# 08_FPGA.net
KiCad netlist of a schematic drawn in Altium Designer
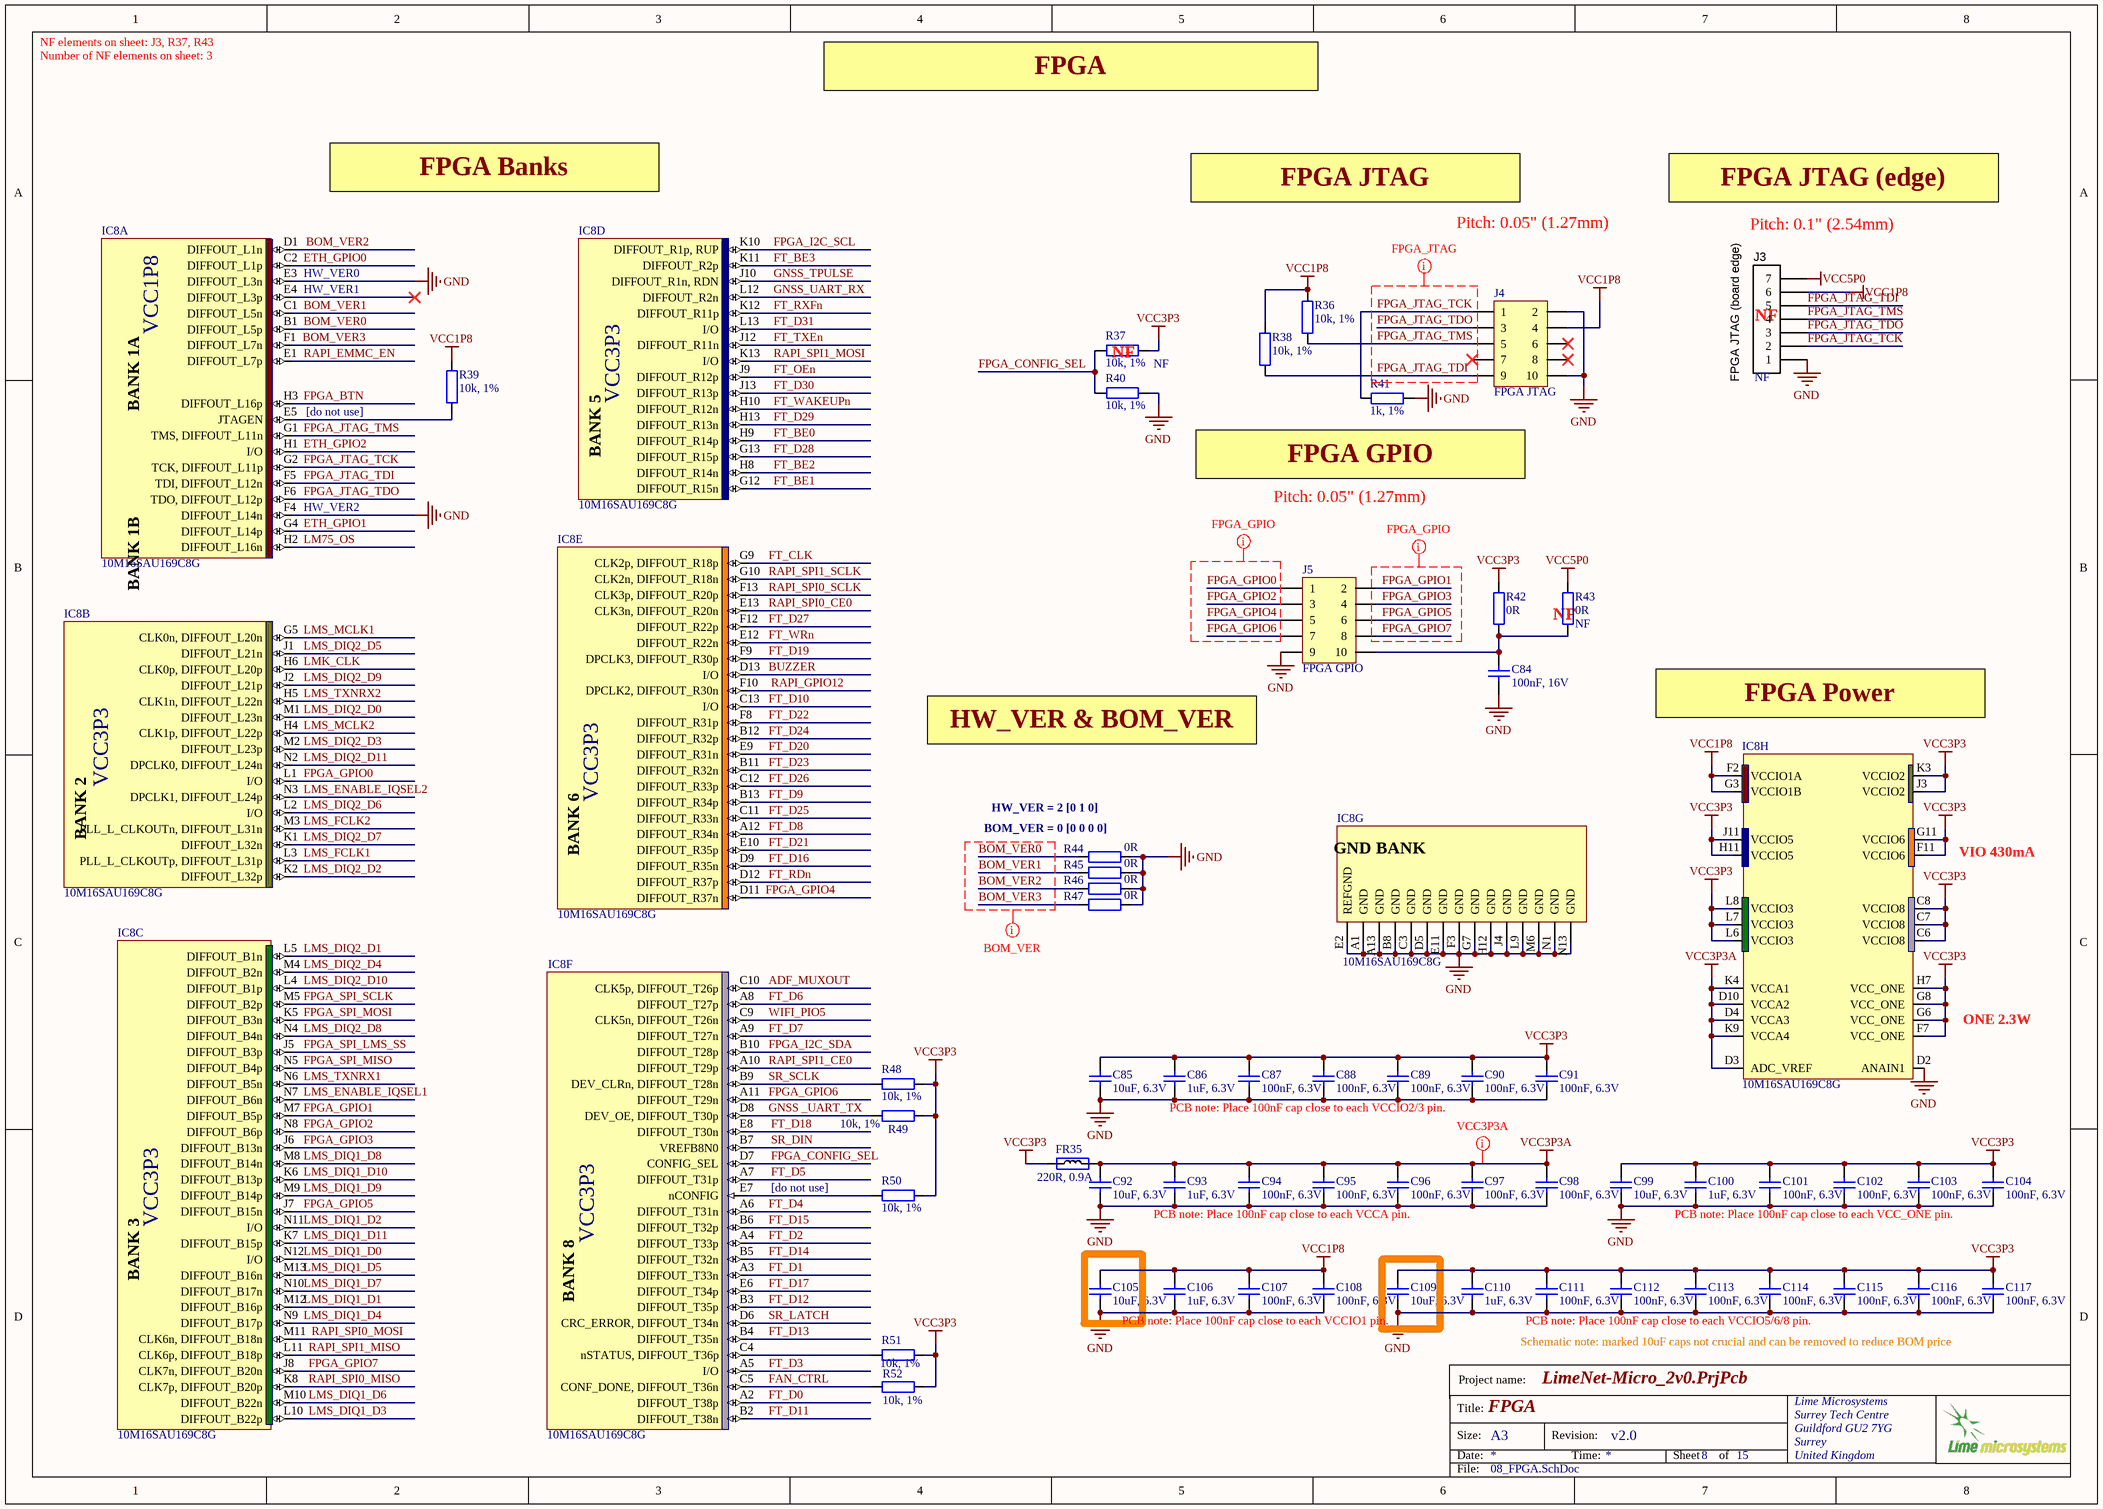
[diagram p0: 08_FPGA.SchDoc]

(export (version "E")
  (design (tool "Eeschema 10.0.6"))
  (components
    (comp (ref "C84")
      (value "100nF, 16V")
      (footprint "CAP0402")
      (fields
        (field (name "MANUFACTURER") "Murata Electronics")
        (field (name "TOLERANCE") "10 %")
        (field (name "MANUFACTURER PART NUMBER") "GRM155R71C104KA88D")
      )
      (libsource (lib "LimeMicroAltiumLib_schLib") (part "Cap_0402"))
    )
    (comp (ref "C85")
      (value "10uF, 6.3V")
      (footprint "CAP0603")
      (fields (field (name "TOLERANCE") "±20%") (field (name "MANUFACTURER") "Yageo"))
      (libsource (lib "LimeFPGAboard_schLib") (part "Cap_0603"))
    )
    (comp (ref "C86")
      (value "1uF, 6.3V")
      (footprint "CAP0201")
      (fields (field (name "TOLERANCE") "±20%") (field (name "MANUFACTURER") "TDK Corporation"))
      (libsource (lib "LimeMicroAltiumLib_schLib") (part "Cap_0402"))
    )
    (comp (ref "C87")
      (value "100nF, 6.3V")
      (footprint "CAP0201")
      (fields (field (name "MANUFACTURER") "Murata") (field (name "TOLERANCE") "10 %"))
      (libsource (lib "LimeMicroAltiumLib_schLib") (part "Cap_0402"))
    )
    (comp (ref "C88")
      (value "100nF, 6.3V")
      (footprint "CAP0201")
      (fields (field (name "MANUFACTURER") "Murata") (field (name "TOLERANCE") "10 %"))
      (libsource (lib "LimeMicroAltiumLib_schLib") (part "Cap_0402"))
    )
    (comp (ref "C89")
      (value "100nF, 6.3V")
      (footprint "CAP0201")
      (fields (field (name "MANUFACTURER") "Murata") (field (name "TOLERANCE") "10 %"))
      (libsource (lib "LimeMicroAltiumLib_schLib") (part "Cap_0402"))
    )
    (comp (ref "C90")
      (value "100nF, 6.3V")
      (footprint "CAP0201")
      (fields (field (name "MANUFACTURER") "Murata") (field (name "TOLERANCE") "10 %"))
      (libsource (lib "LimeMicroAltiumLib_schLib") (part "Cap_0402"))
    )
    (comp (ref "C91")
      (value "100nF, 6.3V")
      (footprint "CAP0201")
      (fields (field (name "MANUFACTURER") "Murata") (field (name "TOLERANCE") "10 %"))
      (libsource (lib "LimeMicroAltiumLib_schLib") (part "Cap_0402"))
    )
    (comp (ref "C92")
      (value "10uF, 6.3V")
      (footprint "CAP0603")
      (fields (field (name "TOLERANCE") "±20%") (field (name "MANUFACTURER") "Yageo"))
      (libsource (lib "LimeFPGAboard_schLib") (part "Cap_0603"))
    )
    (comp (ref "C93")
      (value "1uF, 6.3V")
      (footprint "CAP0201")
      (fields (field (name "TOLERANCE") "±20%") (field (name "MANUFACTURER") "TDK Corporation"))
      (libsource (lib "LimeMicroAltiumLib_schLib") (part "Cap_0402"))
    )
    (comp (ref "C94")
      (value "100nF, 6.3V")
      (footprint "CAP0201")
      (fields (field (name "MANUFACTURER") "Murata") (field (name "TOLERANCE") "10 %"))
      (libsource (lib "LimeMicroAltiumLib_schLib") (part "Cap_0402"))
    )
    (comp (ref "C95")
      (value "100nF, 6.3V")
      (footprint "CAP0201")
      (fields (field (name "MANUFACTURER") "Murata") (field (name "TOLERANCE") "10 %"))
      (libsource (lib "LimeMicroAltiumLib_schLib") (part "Cap_0402"))
    )
    (comp (ref "C96")
      (value "100nF, 6.3V")
      (footprint "CAP0201")
      (fields (field (name "MANUFACTURER") "Murata") (field (name "TOLERANCE") "10 %"))
      (libsource (lib "LimeMicroAltiumLib_schLib") (part "Cap_0402"))
    )
    (comp (ref "C97")
      (value "100nF, 6.3V")
      (footprint "CAP0201")
      (fields (field (name "MANUFACTURER") "Murata") (field (name "TOLERANCE") "10 %"))
      (libsource (lib "LimeMicroAltiumLib_schLib") (part "Cap_0402"))
    )
    (comp (ref "C98")
      (value "100nF, 6.3V")
      (footprint "CAP0201")
      (fields (field (name "MANUFACTURER") "Murata") (field (name "TOLERANCE") "10 %"))
      (libsource (lib "LimeMicroAltiumLib_schLib") (part "Cap_0402"))
    )
    (comp (ref "C99")
      (value "10uF, 6.3V")
      (footprint "CAP0603")
      (fields (field (name "TOLERANCE") "±20%") (field (name "MANUFACTURER") "Yageo"))
      (libsource (lib "LimeFPGAboard_schLib") (part "Cap_0603"))
    )
    (comp (ref "C100")
      (value "1uF, 6.3V")
      (footprint "CAP0201")
      (fields (field (name "TOLERANCE") "±20%") (field (name "MANUFACTURER") "TDK Corporation"))
      (libsource (lib "LimeMicroAltiumLib_schLib") (part "Cap_0402"))
    )
    (comp (ref "C101")
      (value "100nF, 6.3V")
      (footprint "CAP0201")
      (fields (field (name "MANUFACTURER") "Murata") (field (name "TOLERANCE") "10 %"))
      (libsource (lib "LimeMicroAltiumLib_schLib") (part "Cap_0402"))
    )
    (comp (ref "C102")
      (value "100nF, 6.3V")
      (footprint "CAP0201")
      (fields (field (name "MANUFACTURER") "Murata") (field (name "TOLERANCE") "10 %"))
      (libsource (lib "LimeMicroAltiumLib_schLib") (part "Cap_0402"))
    )
    (comp (ref "C103")
      (value "100nF, 6.3V")
      (footprint "CAP0201")
      (fields (field (name "MANUFACTURER") "Murata") (field (name "TOLERANCE") "10 %"))
      (libsource (lib "LimeMicroAltiumLib_schLib") (part "Cap_0402"))
    )
    (comp (ref "C104")
      (value "100nF, 6.3V")
      (footprint "CAP0201")
      (fields (field (name "MANUFACTURER") "Murata") (field (name "TOLERANCE") "10 %"))
      (libsource (lib "LimeMicroAltiumLib_schLib") (part "Cap_0402"))
    )
    (comp (ref "C105")
      (value "10uF, 6.3V")
      (footprint "CAP0603")
      (fields (field (name "TOLERANCE") "±20%") (field (name "MANUFACTURER") "Yageo"))
      (libsource (lib "LimeFPGAboard_schLib") (part "Cap_0603"))
    )
    (comp (ref "C106")
      (value "1uF, 6.3V")
      (footprint "CAP0201")
      (fields (field (name "TOLERANCE") "±20%") (field (name "MANUFACTURER") "TDK Corporation"))
      (libsource (lib "LimeMicroAltiumLib_schLib") (part "Cap_0402"))
    )
    (comp (ref "C107")
      (value "100nF, 6.3V")
      (footprint "CAP0201")
      (fields (field (name "MANUFACTURER") "Murata") (field (name "TOLERANCE") "10 %"))
      (libsource (lib "LimeMicroAltiumLib_schLib") (part "Cap_0402"))
    )
    (comp (ref "C108")
      (value "100nF, 6.3V")
      (footprint "CAP0201")
      (fields (field (name "MANUFACTURER") "Murata") (field (name "TOLERANCE") "10 %"))
      (libsource (lib "LimeMicroAltiumLib_schLib") (part "Cap_0402"))
    )
    (comp (ref "C109")
      (value "10uF, 6.3V")
      (footprint "CAP0603")
      (fields (field (name "TOLERANCE") "±20%") (field (name "MANUFACTURER") "Yageo"))
      (libsource (lib "LimeFPGAboard_schLib") (part "Cap_0603"))
    )
    (comp (ref "C110")
      (value "1uF, 6.3V")
      (footprint "CAP0201")
      (fields (field (name "TOLERANCE") "±20%") (field (name "MANUFACTURER") "TDK Corporation"))
      (libsource (lib "LimeMicroAltiumLib_schLib") (part "Cap_0402"))
    )
    (comp (ref "C111")
      (value "100nF, 6.3V")
      (footprint "CAP0201")
      (fields (field (name "MANUFACTURER") "Murata") (field (name "TOLERANCE") "10 %"))
      (libsource (lib "LimeMicroAltiumLib_schLib") (part "Cap_0402"))
    )
    (comp (ref "C112")
      (value "100nF, 6.3V")
      (footprint "CAP0201")
      (fields (field (name "MANUFACTURER") "Murata") (field (name "TOLERANCE") "10 %"))
      (libsource (lib "LimeMicroAltiumLib_schLib") (part "Cap_0402"))
    )
    (comp (ref "C113")
      (value "100nF, 6.3V")
      (footprint "CAP0201")
      (fields (field (name "MANUFACTURER") "Murata") (field (name "TOLERANCE") "10 %"))
      (libsource (lib "LimeMicroAltiumLib_schLib") (part "Cap_0402"))
    )
    (comp (ref "C114")
      (value "100nF, 6.3V")
      (footprint "CAP0201")
      (fields (field (name "MANUFACTURER") "Murata") (field (name "TOLERANCE") "10 %"))
      (libsource (lib "LimeMicroAltiumLib_schLib") (part "Cap_0402"))
    )
    (comp (ref "C115")
      (value "100nF, 6.3V")
      (footprint "CAP0201")
      (fields (field (name "MANUFACTURER") "Murata") (field (name "TOLERANCE") "10 %"))
      (libsource (lib "LimeMicroAltiumLib_schLib") (part "Cap_0402"))
    )
    (comp (ref "C116")
      (value "100nF, 6.3V")
      (footprint "CAP0201")
      (fields (field (name "MANUFACTURER") "Murata") (field (name "TOLERANCE") "10 %"))
      (libsource (lib "LimeMicroAltiumLib_schLib") (part "Cap_0402"))
    )
    (comp (ref "C117")
      (value "100nF, 6.3V")
      (footprint "CAP0201")
      (fields (field (name "MANUFACTURER") "Murata") (field (name "TOLERANCE") "10 %"))
      (libsource (lib "LimeMicroAltiumLib_schLib") (part "Cap_0402"))
    )
    (comp (ref "FR35")
      (value "220R, 0.9A")
      (footprint "RES0402")
      (fields (field (name "MANUFACTURER") "TDK Corporation"))
      (libsource (lib "LimeFPGAboard_schLib") (part "Ferrite"))
    )
    (comp (ref "IC8")
      (value "10M16SAU169C8G")
      (footprint "10M16SAU169C8G")
      (fields (field (name "MANUFACTURER") "Altera"))
      (libsource (lib "LimeMicroAltiumLib_schLib") (part "10M16SAU169C8G"))
    )
    (comp (ref "J3")
      (value "FPGA JTAG (board edge)")
      (footprint "Header7x1_TH")
      (description "Header, 7-pin")
      (fields (field (name "MANUFACTURER") "Sullins Connector Solutions") (field (name "ASSEMBLY INFO") "NF"))
      (libsource (lib "LimeMicroAltiumLib_schLib") (part "Header7P"))
    )
    (comp (ref "J4")
      (value "FPGA JTAG")
      (footprint "SWD_10_pin")
      (description "Header, 5-Pin, Dual row")
      (fields (field (name "MANUFACTURER") "Harwin Inc"))
      (libsource (lib "LimeMicroAltiumLib_schLib") (part "Header 5X2_SWD"))
    )
    (comp (ref "J5")
      (value "FPGA GPIO")
      (footprint "SWD_10_pin")
      (description "Header, 5-Pin, Dual row")
      (fields (field (name "MANUFACTURER") "Harwin Inc"))
      (libsource (lib "LimeMicroAltiumLib_schLib") (part "Header 5X2_SWD"))
    )
    (comp (ref "R36")
      (value "10k, 1%")
      (footprint "RES0402")
      (fields (field (name "MANUFACTURER") "Yageo") (field (name "TOLERANCE") "±1%"))
      (libsource (lib "LimeMicroAltiumLib_schLib") (part "Res_0402"))
    )
    (comp (ref "R37")
      (value "10k, 1%")
      (footprint "RES0402")
      (fields
        (field (name "ASSEMBLY INFO") "NF")
        (field (name "MANUFACTURER") "Yageo")
        (field (name "TOLERANCE") "±1%")
      )
      (libsource (lib "LimeMicroAltiumLib_schLib") (part "Res_0402"))
    )
    (comp (ref "R38")
      (value "10k, 1%")
      (footprint "RES0402")
      (fields (field (name "MANUFACTURER") "Yageo") (field (name "TOLERANCE") "±1%"))
      (libsource (lib "LimeMicroAltiumLib_schLib") (part "Res_0402"))
    )
    (comp (ref "R39")
      (value "10k, 1%")
      (footprint "RES0402")
      (fields (field (name "MANUFACTURER") "Yageo") (field (name "TOLERANCE") "±1%"))
      (libsource (lib "LimeMicroAltiumLib_schLib") (part "Res_0402"))
    )
    (comp (ref "R40")
      (value "10k, 1%")
      (footprint "RES0402")
      (fields (field (name "MANUFACTURER") "Yageo") (field (name "TOLERANCE") "±1%"))
      (libsource (lib "LimeMicroAltiumLib_schLib") (part "Res_0402"))
    )
    (comp (ref "R41")
      (value "1k, 1%")
      (footprint "RES0402")
      (fields (field (name "MANUFACTURER") "Stackpole Electronics Inc") (field (name "TOLERANCE") "±1%"))
      (libsource (lib "LimeMicroAltiumLib_schLib") (part "Res_0402"))
    )
    (comp (ref "R42")
      (value "0R")
      (footprint "RES0402")
      (fields (field (name "MANUFACTURER") "Yageo"))
      (libsource (lib "LimeFPGAboard_schLib") (part "Res_0402"))
    )
    (comp (ref "R43")
      (value "0R")
      (footprint "RES0402")
      (fields (field (name "MANUFACTURER") "Yageo") (field (name "ASSEMBLY INFO") "NF"))
      (libsource (lib "LimeFPGAboard_schLib") (part "Res_0402"))
    )
    (comp (ref "R44")
      (value "0R")
      (footprint "RES0402")
      (fields (field (name "MANUFACTURER") "Yageo"))
      (libsource (lib "LimeFPGAboard_schLib") (part "Res_0402"))
    )
    (comp (ref "R45")
      (value "0R")
      (footprint "RES0402")
      (fields (field (name "MANUFACTURER") "Yageo"))
      (libsource (lib "LimeFPGAboard_schLib") (part "Res_0402"))
    )
    (comp (ref "R46")
      (value "0R")
      (footprint "RES0402")
      (fields (field (name "MANUFACTURER") "Yageo"))
      (libsource (lib "LimeFPGAboard_schLib") (part "Res_0402"))
    )
    (comp (ref "R47")
      (value "0R")
      (footprint "RES0402")
      (fields (field (name "MANUFACTURER") "Yageo"))
      (libsource (lib "LimeFPGAboard_schLib") (part "Res_0402"))
    )
    (comp (ref "R48")
      (value "10k, 1%")
      (footprint "RES0402")
      (fields (field (name "MANUFACTURER") "Yageo") (field (name "TOLERANCE") "±1%"))
      (libsource (lib "LimeMicroAltiumLib_schLib") (part "Res_0402"))
    )
    (comp (ref "R49")
      (value "10k, 1%")
      (footprint "RES0402")
      (fields (field (name "MANUFACTURER") "Yageo") (field (name "TOLERANCE") "±1%"))
      (libsource (lib "LimeMicroAltiumLib_schLib") (part "Res_0402"))
    )
    (comp (ref "R50")
      (value "10k, 1%")
      (footprint "RES0402")
      (fields (field (name "MANUFACTURER") "Yageo") (field (name "TOLERANCE") "±1%"))
      (libsource (lib "LimeMicroAltiumLib_schLib") (part "Res_0402"))
    )
    (comp (ref "R51")
      (value "10k, 1%")
      (footprint "RES0402")
      (fields (field (name "MANUFACTURER") "Yageo") (field (name "TOLERANCE") "±1%"))
      (libsource (lib "LimeMicroAltiumLib_schLib") (part "Res_0402"))
    )
    (comp (ref "R52")
      (value "10k, 1%")
      (footprint "RES0402")
      (fields (field (name "MANUFACTURER") "Yageo") (field (name "TOLERANCE") "±1%"))
      (libsource (lib "LimeMicroAltiumLib_schLib") (part "Res_0402"))
    )
  )
  (nets
    (net (code "1") (name "/ADF_MUXOUT") (class "Default")
      (node (ref "IC8") (pin "C10") (pinfunction "CLK5p,_DIFFOUT_T26p_C10") (pintype "bidirectional"))
    )
    (net (code "2") (name "/BOM_VER0") (class "Default")
      (node (ref "IC8") (pin "B1") (pinfunction "DIFFOUT_L5p_B1") (pintype "bidirectional"))
      (node (ref "R44") (pin "2") (pinfunction "2_2") (pintype "passive"))
    )
    (net (code "3") (name "/BOM_VER1") (class "Default")
      (node (ref "IC8") (pin "C1") (pinfunction "DIFFOUT_L5n_C1") (pintype "bidirectional"))
      (node (ref "R45") (pin "2") (pinfunction "2_2") (pintype "passive"))
    )
    (net (code "4") (name "/BOM_VER2") (class "Default")
      (node (ref "IC8") (pin "D1") (pinfunction "DIFFOUT_L1n_D1") (pintype "bidirectional"))
      (node (ref "R46") (pin "2") (pinfunction "2_2") (pintype "passive"))
    )
    (net (code "5") (name "/BOM_VER3") (class "Default")
      (node (ref "IC8") (pin "F1") (pinfunction "DIFFOUT_L7n_F1") (pintype "bidirectional"))
      (node (ref "R47") (pin "2") (pinfunction "2_2") (pintype "passive"))
    )
    (net (code "6") (name "/BUZZER") (class "Default")
      (node (ref "IC8") (pin "D13") (pinfunction "I/O_D13") (pintype "bidirectional"))
    )
    (net (code "7") (name "/ETH_GPIO0") (class "Default")
      (node (ref "IC8") (pin "C2") (pinfunction "DIFFOUT_L1p_C2") (pintype "bidirectional"))
    )
    (net (code "8") (name "/ETH_GPIO1") (class "Default")
      (node (ref "IC8") (pin "G4") (pinfunction "DIFFOUT_L14p_G4") (pintype "bidirectional"))
    )
    (net (code "9") (name "/ETH_GPIO2") (class "Default")
      (node (ref "IC8") (pin "H1") (pinfunction "I/O_H1") (pintype "bidirectional"))
    )
    (net (code "10") (name "/FAN_CTRL") (class "Default")
      (node (ref "IC8") (pin "C5") (pinfunction "CONF_DONE,_DIFFOUT_T36n_C5") (pintype "bidirectional"))
      (node (ref "R52") (pin "2") (pinfunction "2_2") (pintype "passive"))
    )
    (net (code "11") (name "/FPGA_BTN") (class "Default")
      (node (ref "IC8") (pin "H3") (pinfunction "DIFFOUT_L16p_H3") (pintype "bidirectional"))
    )
    (net (code "12") (name "/FPGA_CONFIG_SEL") (class "Default")
      (node (ref "IC8") (pin "D7") (pinfunction "CONFIG_SEL_D7") (pintype "bidirectional"))
      (node (ref "R37") (pin "2") (pinfunction "2_2") (pintype "passive"))
      (node (ref "R40") (pin "2") (pinfunction "2_2") (pintype "passive"))
    )
    (net (code "13") (name "/FPGA_GPIO0") (class "Default")
      (node (ref "IC8") (pin "L1") (pinfunction "I/O_L1") (pintype "bidirectional"))
      (node (ref "J5") (pin "1") (pinfunction "1_1") (pintype "passive"))
    )
    (net (code "14") (name "/FPGA_GPIO1") (class "Default")
      (node (ref "IC8") (pin "M7") (pinfunction "DIFFOUT_B5p_M7") (pintype "bidirectional"))
      (node (ref "J5") (pin "2") (pinfunction "2_2") (pintype "passive"))
    )
    (net (code "15") (name "/FPGA_GPIO2") (class "Default")
      (node (ref "IC8") (pin "N8") (pinfunction "DIFFOUT_B6p_N8") (pintype "bidirectional"))
      (node (ref "J5") (pin "3") (pinfunction "3_3") (pintype "passive"))
    )
    (net (code "16") (name "/FPGA_GPIO3") (class "Default")
      (node (ref "IC8") (pin "J6") (pinfunction "DIFFOUT_B13n_J6") (pintype "bidirectional"))
      (node (ref "J5") (pin "4") (pinfunction "4_4") (pintype "passive"))
    )
    (net (code "17") (name "/FPGA_GPIO4") (class "Default")
      (node (ref "IC8") (pin "D11") (pinfunction "DIFFOUT_R37n_D11") (pintype "bidirectional"))
      (node (ref "J5") (pin "5") (pinfunction "5_5") (pintype "passive"))
    )
    (net (code "18") (name "/FPGA_GPIO5") (class "Default")
      (node (ref "IC8") (pin "J7") (pinfunction "DIFFOUT_B15n_J7") (pintype "bidirectional"))
      (node (ref "J5") (pin "6") (pinfunction "6_6") (pintype "passive"))
    )
    (net (code "19") (name "/FPGA_GPIO6") (class "Default")
      (node (ref "IC8") (pin "A11") (pinfunction "DIFFOUT_T29n_A11") (pintype "bidirectional"))
      (node (ref "J5") (pin "7") (pinfunction "7_7") (pintype "passive"))
    )
    (net (code "20") (name "/FPGA_GPIO7") (class "Default")
      (node (ref "IC8") (pin "J8") (pinfunction "CLK7n,_DIFFOUT_B20n_J8") (pintype "bidirectional"))
      (node (ref "J5") (pin "8") (pinfunction "8_8") (pintype "passive"))
    )
    (net (code "21") (name "/FPGA_I2C_SCL") (class "Default")
      (node (ref "IC8") (pin "K10") (pinfunction "DIFFOUT_R1p,_RUP_K10") (pintype "bidirectional"))
    )
    (net (code "22") (name "/FPGA_I2C_SDA") (class "Default")
      (node (ref "IC8") (pin "B10") (pinfunction "DIFFOUT_T28p_B10") (pintype "bidirectional"))
    )
    (net (code "23") (name "/FPGA_JTAG_TCK") (class "Default")
      (node (ref "IC8") (pin "G2") (pinfunction "TCK,_DIFFOUT_L11p_G2") (pintype "bidirectional"))
      (node (ref "J3") (pin "2") (pinfunction "2_2") (pintype "passive"))
      (node (ref "J4") (pin "1") (pinfunction "1_1") (pintype "passive"))
      (node (ref "R41") (pin "1") (pinfunction "1_1") (pintype "passive"))
    )
    (net (code "24") (name "/FPGA_JTAG_TDI") (class "Default")
      (node (ref "IC8") (pin "F5") (pinfunction "TDI,_DIFFOUT_L12n_F5") (pintype "bidirectional"))
      (node (ref "J3") (pin "5") (pinfunction "5_5") (pintype "passive"))
      (node (ref "J4") (pin "9") (pinfunction "9_9") (pintype "passive"))
      (node (ref "R38") (pin "1") (pinfunction "1_1") (pintype "passive"))
    )
    (net (code "25") (name "/FPGA_JTAG_TDO") (class "Default")
      (node (ref "IC8") (pin "F6") (pinfunction "TDO,_DIFFOUT_L12p_F6") (pintype "bidirectional"))
      (node (ref "J3") (pin "3") (pinfunction "3_3") (pintype "passive"))
      (node (ref "J4") (pin "3") (pinfunction "3_3") (pintype "passive"))
    )
    (net (code "26") (name "/FPGA_JTAG_TMS") (class "Default")
      (node (ref "IC8") (pin "G1") (pinfunction "TMS,_DIFFOUT_L11n_G1") (pintype "bidirectional"))
      (node (ref "J3") (pin "4") (pinfunction "4_4") (pintype "passive"))
      (node (ref "J4") (pin "5") (pinfunction "5_5") (pintype "passive"))
      (node (ref "R36") (pin "1") (pinfunction "1_1") (pintype "passive"))
    )
    (net (code "27") (name "/FPGA_SPI_LMS_SS") (class "Default")
      (node (ref "IC8") (pin "J5") (pinfunction "DIFFOUT_B3p_J5") (pintype "bidirectional"))
    )
    (net (code "28") (name "/FPGA_SPI_MISO") (class "Default")
      (node (ref "IC8") (pin "N5") (pinfunction "DIFFOUT_B4p_N5") (pintype "bidirectional"))
    )
    (net (code "29") (name "/FPGA_SPI_MOSI") (class "Default")
      (node (ref "IC8") (pin "K5") (pinfunction "DIFFOUT_B3n_K5") (pintype "bidirectional"))
    )
    (net (code "30") (name "/FPGA_SPI_SCLK") (class "Default")
      (node (ref "IC8") (pin "M5") (pinfunction "DIFFOUT_B2p_M5") (pintype "bidirectional"))
    )
    (net (code "31") (name "/FT_BE0") (class "Default")
      (node (ref "IC8") (pin "H9") (pinfunction "DIFFOUT_R14p_H9") (pintype "bidirectional"))
    )
    (net (code "32") (name "/FT_BE1") (class "Default")
      (node (ref "IC8") (pin "G12") (pinfunction "DIFFOUT_R15n_G12") (pintype "bidirectional"))
    )
    (net (code "33") (name "/FT_BE2") (class "Default")
      (node (ref "IC8") (pin "H8") (pinfunction "DIFFOUT_R14n_H8") (pintype "bidirectional"))
    )
    (net (code "34") (name "/FT_BE3") (class "Default")
      (node (ref "IC8") (pin "K11") (pinfunction "DIFFOUT_R2p_K11") (pintype "bidirectional"))
    )
    (net (code "35") (name "/FT_CLK") (class "Default")
      (node (ref "IC8") (pin "G9") (pinfunction "CLK2p,_DIFFOUT_R18p_G9") (pintype "bidirectional"))
    )
    (net (code "36") (name "/FT_D0") (class "Default")
      (node (ref "IC8") (pin "A2") (pinfunction "DIFFOUT_T38p_A2") (pintype "bidirectional"))
    )
    (net (code "37") (name "/FT_D1") (class "Default")
      (node (ref "IC8") (pin "A3") (pinfunction "DIFFOUT_T33n_A3") (pintype "bidirectional"))
    )
    (net (code "38") (name "/FT_D2") (class "Default")
      (node (ref "IC8") (pin "A4") (pinfunction "DIFFOUT_T33p_A4") (pintype "bidirectional"))
    )
    (net (code "39") (name "/FT_D3") (class "Default")
      (node (ref "IC8") (pin "A5") (pinfunction "I/O_A5") (pintype "bidirectional"))
    )
    (net (code "40") (name "/FT_D4") (class "Default")
      (node (ref "IC8") (pin "A6") (pinfunction "DIFFOUT_T31n_A6") (pintype "bidirectional"))
    )
    (net (code "41") (name "/FT_D5") (class "Default")
      (node (ref "IC8") (pin "A7") (pinfunction "DIFFOUT_T31p_A7") (pintype "bidirectional"))
    )
    (net (code "42") (name "/FT_D6") (class "Default")
      (node (ref "IC8") (pin "A8") (pinfunction "DIFFOUT_T27p_A8") (pintype "bidirectional"))
    )
    (net (code "43") (name "/FT_D7") (class "Default")
      (node (ref "IC8") (pin "A9") (pinfunction "DIFFOUT_T27n_A9") (pintype "bidirectional"))
    )
    (net (code "44") (name "/FT_D8") (class "Default")
      (node (ref "IC8") (pin "A12") (pinfunction "DIFFOUT_R34n_A12") (pintype "bidirectional"))
    )
    (net (code "45") (name "/FT_D9") (class "Default")
      (node (ref "IC8") (pin "B13") (pinfunction "DIFFOUT_R34p_B13") (pintype "bidirectional"))
    )
    (net (code "46") (name "/FT_D10") (class "Default")
      (node (ref "IC8") (pin "C13") (pinfunction "I/O_C13") (pintype "bidirectional"))
    )
    (net (code "47") (name "/FT_D11") (class "Default")
      (node (ref "IC8") (pin "B2") (pinfunction "DIFFOUT_T38n_B2") (pintype "bidirectional"))
    )
    (net (code "48") (name "/FT_D12") (class "Default")
      (node (ref "IC8") (pin "B3") (pinfunction "DIFFOUT_T35p_B3") (pintype "bidirectional"))
    )
    (net (code "49") (name "/FT_D13") (class "Default")
      (node (ref "IC8") (pin "B4") (pinfunction "DIFFOUT_T35n_B4") (pintype "bidirectional"))
    )
    (net (code "50") (name "/FT_D14") (class "Default")
      (node (ref "IC8") (pin "B5") (pinfunction "DIFFOUT_T32n_B5") (pintype "bidirectional"))
    )
    (net (code "51") (name "/FT_D15") (class "Default")
      (node (ref "IC8") (pin "B6") (pinfunction "DIFFOUT_T32p_B6") (pintype "bidirectional"))
    )
    (net (code "52") (name "/FT_D16") (class "Default")
      (node (ref "IC8") (pin "D9") (pinfunction "DIFFOUT_R35n_D9") (pintype "bidirectional"))
    )
    (net (code "53") (name "/FT_D17") (class "Default")
      (node (ref "IC8") (pin "E6") (pinfunction "DIFFOUT_T34p_E6") (pintype "bidirectional"))
    )
    (net (code "54") (name "/FT_D18") (class "Default")
      (node (ref "IC8") (pin "E8") (pinfunction "DIFFOUT_T30n_E8") (pintype "bidirectional"))
    )
    (net (code "55") (name "/FT_D19") (class "Default")
      (node (ref "IC8") (pin "F9") (pinfunction "DPCLK3,_DIFFOUT_R30p_F9") (pintype "bidirectional"))
    )
    (net (code "56") (name "/FT_D20") (class "Default")
      (node (ref "IC8") (pin "E9") (pinfunction "DIFFOUT_R31n_E9") (pintype "bidirectional"))
    )
    (net (code "57") (name "/FT_D21") (class "Default")
      (node (ref "IC8") (pin "E10") (pinfunction "DIFFOUT_R35p_E10") (pintype "bidirectional"))
    )
    (net (code "58") (name "/FT_D22") (class "Default")
      (node (ref "IC8") (pin "F8") (pinfunction "DIFFOUT_R31p_F8") (pintype "bidirectional"))
    )
    (net (code "59") (name "/FT_D23") (class "Default")
      (node (ref "IC8") (pin "B11") (pinfunction "DIFFOUT_R32n_B11") (pintype "bidirectional"))
    )
    (net (code "60") (name "/FT_D24") (class "Default")
      (node (ref "IC8") (pin "B12") (pinfunction "DIFFOUT_R32p_B12") (pintype "bidirectional"))
    )
    (net (code "61") (name "/FT_D25") (class "Default")
      (node (ref "IC8") (pin "C11") (pinfunction "DIFFOUT_R33n_C11") (pintype "bidirectional"))
    )
    (net (code "62") (name "/FT_D26") (class "Default")
      (node (ref "IC8") (pin "C12") (pinfunction "DIFFOUT_R33p_C12") (pintype "bidirectional"))
    )
    (net (code "63") (name "/FT_D27") (class "Default")
      (node (ref "IC8") (pin "F12") (pinfunction "DIFFOUT_R22p_F12") (pintype "bidirectional"))
    )
    (net (code "64") (name "/FT_D28") (class "Default")
      (node (ref "IC8") (pin "G13") (pinfunction "DIFFOUT_R15p_G13") (pintype "bidirectional"))
    )
    (net (code "65") (name "/FT_D29") (class "Default")
      (node (ref "IC8") (pin "H13") (pinfunction "DIFFOUT_R13n_H13") (pintype "bidirectional"))
    )
    (net (code "66") (name "/FT_D30") (class "Default")
      (node (ref "IC8") (pin "J13") (pinfunction "DIFFOUT_R13p_J13") (pintype "bidirectional"))
    )
    (net (code "67") (name "/FT_D31") (class "Default")
      (node (ref "IC8") (pin "L13") (pinfunction "I/O_L13") (pintype "bidirectional"))
    )
    (net (code "68") (name "/FT_OEn") (class "Default")
      (node (ref "IC8") (pin "J9") (pinfunction "DIFFOUT_R12p_J9") (pintype "bidirectional"))
    )
    (net (code "69") (name "/FT_RDn") (class "Default")
      (node (ref "IC8") (pin "D12") (pinfunction "DIFFOUT_R37p_D12") (pintype "bidirectional"))
    )
    (net (code "70") (name "/FT_RXFn") (class "Default")
      (node (ref "IC8") (pin "K12") (pinfunction "DIFFOUT_R11p_K12") (pintype "bidirectional"))
    )
    (net (code "71") (name "/FT_TXEn") (class "Default")
      (node (ref "IC8") (pin "J12") (pinfunction "DIFFOUT_R11n_J12") (pintype "bidirectional"))
    )
    (net (code "72") (name "/FT_WAKEUPn") (class "Default")
      (node (ref "IC8") (pin "H10") (pinfunction "DIFFOUT_R12n_H10") (pintype "bidirectional"))
    )
    (net (code "73") (name "/FT_WRn") (class "Default")
      (node (ref "IC8") (pin "E12") (pinfunction "DIFFOUT_R22n_E12") (pintype "bidirectional"))
    )
    (net (code "74") (name "/GNSS _UART_TX") (class "Default")
      (node (ref "IC8") (pin "D8") (pinfunction "DEV_OE,_DIFFOUT_T30p_D8") (pintype "bidirectional"))
      (node (ref "R49") (pin "2") (pinfunction "2_2") (pintype "passive"))
    )
    (net (code "75") (name "/GNSS_TPULSE") (class "Default")
      (node (ref "IC8") (pin "J10") (pinfunction "DIFFOUT_R1n,_RDN_J10") (pintype "bidirectional"))
    )
    (net (code "76") (name "/GNSS_UART_RX") (class "Default")
      (node (ref "IC8") (pin "L12") (pinfunction "DIFFOUT_R2n_L12") (pintype "bidirectional"))
    )
    (net (code "77") (name "/LM75_OS") (class "Default")
      (node (ref "IC8") (pin "H2") (pinfunction "DIFFOUT_L16n_H2") (pintype "bidirectional"))
    )
    (net (code "78") (name "/LMK_CLK") (class "Default")
      (node (ref "IC8") (pin "H6") (pinfunction "CLK0p,_DIFFOUT_L20p_H6") (pintype "bidirectional"))
    )
    (net (code "79") (name "/LMS_DIQ1_D0") (class "Default")
      (node (ref "IC8") (pin "N12") (pinfunction "I/O_N12") (pintype "bidirectional"))
    )
    (net (code "80") (name "/LMS_DIQ1_D1") (class "Default")
      (node (ref "IC8") (pin "M12") (pinfunction "DIFFOUT_B16p_M12") (pintype "bidirectional"))
    )
    (net (code "81") (name "/LMS_DIQ1_D2") (class "Default")
      (node (ref "IC8") (pin "N11") (pinfunction "I/O_N11") (pintype "bidirectional"))
    )
    (net (code "82") (name "/LMS_DIQ1_D3") (class "Default")
      (node (ref "IC8") (pin "L10") (pinfunction "DIFFOUT_B22p_L10") (pintype "bidirectional"))
    )
    (net (code "83") (name "/LMS_DIQ1_D4") (class "Default")
      (node (ref "IC8") (pin "N9") (pinfunction "DIFFOUT_B17p_N9") (pintype "bidirectional"))
    )
    (net (code "84") (name "/LMS_DIQ1_D5") (class "Default")
      (node (ref "IC8") (pin "M13") (pinfunction "DIFFOUT_B16n_M13") (pintype "bidirectional"))
    )
    (net (code "85") (name "/LMS_DIQ1_D6") (class "Default")
      (node (ref "IC8") (pin "M10") (pinfunction "DIFFOUT_B22n_M10") (pintype "bidirectional"))
    )
    (net (code "86") (name "/LMS_DIQ1_D7") (class "Default")
      (node (ref "IC8") (pin "N10") (pinfunction "DIFFOUT_B17n_N10") (pintype "bidirectional"))
    )
    (net (code "87") (name "/LMS_DIQ1_D8") (class "Default")
      (node (ref "IC8") (pin "M8") (pinfunction "DIFFOUT_B14n_M8") (pintype "bidirectional"))
    )
    (net (code "88") (name "/LMS_DIQ1_D9") (class "Default")
      (node (ref "IC8") (pin "M9") (pinfunction "DIFFOUT_B14p_M9") (pintype "bidirectional"))
    )
    (net (code "89") (name "/LMS_DIQ1_D10") (class "Default")
      (node (ref "IC8") (pin "K6") (pinfunction "DIFFOUT_B13p_K6") (pintype "bidirectional"))
    )
    (net (code "90") (name "/LMS_DIQ1_D11") (class "Default")
      (node (ref "IC8") (pin "K7") (pinfunction "DIFFOUT_B15p_K7") (pintype "bidirectional"))
    )
    (net (code "91") (name "/LMS_DIQ2_D0") (class "Default")
      (node (ref "IC8") (pin "M1") (pinfunction "DIFFOUT_L23n_M1") (pintype "bidirectional"))
    )
    (net (code "92") (name "/LMS_DIQ2_D1") (class "Default")
      (node (ref "IC8") (pin "L5") (pinfunction "DIFFOUT_B1n_L5") (pintype "bidirectional"))
    )
    (net (code "93") (name "/LMS_DIQ2_D2") (class "Default")
      (node (ref "IC8") (pin "K2") (pinfunction "DIFFOUT_L32p_K2") (pintype "bidirectional"))
    )
    (net (code "94") (name "/LMS_DIQ2_D3") (class "Default")
      (node (ref "IC8") (pin "M2") (pinfunction "DIFFOUT_L23p_M2") (pintype "bidirectional"))
    )
    (net (code "95") (name "/LMS_DIQ2_D4") (class "Default")
      (node (ref "IC8") (pin "M4") (pinfunction "DIFFOUT_B2n_M4") (pintype "bidirectional"))
    )
    (net (code "96") (name "/LMS_DIQ2_D5") (class "Default")
      (node (ref "IC8") (pin "J1") (pinfunction "DIFFOUT_L21n_J1") (pintype "bidirectional"))
    )
    (net (code "97") (name "/LMS_DIQ2_D6") (class "Default")
      (node (ref "IC8") (pin "L2") (pinfunction "I/O_L2") (pintype "bidirectional"))
    )
    (net (code "98") (name "/LMS_DIQ2_D7") (class "Default")
      (node (ref "IC8") (pin "K1") (pinfunction "DIFFOUT_L32n_K1") (pintype "bidirectional"))
    )
    (net (code "99") (name "/LMS_DIQ2_D8") (class "Default")
      (node (ref "IC8") (pin "N4") (pinfunction "DIFFOUT_B4n_N4") (pintype "bidirectional"))
    )
    (net (code "100") (name "/LMS_DIQ2_D9") (class "Default")
      (node (ref "IC8") (pin "J2") (pinfunction "DIFFOUT_L21p_J2") (pintype "bidirectional"))
    )
    (net (code "101") (name "/LMS_DIQ2_D10") (class "Default")
      (node (ref "IC8") (pin "L4") (pinfunction "DIFFOUT_B1p_L4") (pintype "bidirectional"))
    )
    (net (code "102") (name "/LMS_DIQ2_D11") (class "Default")
      (node (ref "IC8") (pin "N2") (pinfunction "DPCLK0,_DIFFOUT_L24n_N2") (pintype "bidirectional"))
    )
    (net (code "103") (name "/LMS_ENABLE_IQSEL1") (class "Default")
      (node (ref "IC8") (pin "N7") (pinfunction "DIFFOUT_B6n_N7") (pintype "bidirectional"))
    )
    (net (code "104") (name "/LMS_ENABLE_IQSEL2") (class "Default")
      (node (ref "IC8") (pin "N3") (pinfunction "DPCLK1,_DIFFOUT_L24p_N3") (pintype "bidirectional"))
    )
    (net (code "105") (name "/LMS_FCLK1") (class "Default")
      (node (ref "IC8") (pin "L3") (pinfunction "PLL_L_CLKOUTp,_DIFFOUT_L31p_L3") (pintype "bidirectional"))
    )
    (net (code "106") (name "/LMS_FCLK2") (class "Default")
      (node (ref "IC8") (pin "M3") (pinfunction "PLL_L_CLKOUTn,_DIFFOUT_L31n_M3") (pintype "bidirectional"))
    )
    (net (code "107") (name "/LMS_MCLK1") (class "Default")
      (node (ref "IC8") (pin "G5") (pinfunction "CLK0n,_DIFFOUT_L20n_G5") (pintype "bidirectional"))
    )
    (net (code "108") (name "/LMS_MCLK2") (class "Default")
      (node (ref "IC8") (pin "H4") (pinfunction "CLK1p,_DIFFOUT_L22p_H4") (pintype "bidirectional"))
    )
    (net (code "109") (name "/LMS_TXNRX1") (class "Default")
      (node (ref "IC8") (pin "N6") (pinfunction "DIFFOUT_B5n_N6") (pintype "bidirectional"))
    )
    (net (code "110") (name "/LMS_TXNRX2") (class "Default")
      (node (ref "IC8") (pin "H5") (pinfunction "CLK1n,_DIFFOUT_L22n_H5") (pintype "bidirectional"))
    )
    (net (code "111") (name "/RAPI_EMMC_EN") (class "Default")
      (node (ref "IC8") (pin "E1") (pinfunction "DIFFOUT_L7p_E1") (pintype "bidirectional"))
    )
    (net (code "112") (name "/RAPI_GPIO12") (class "Default")
      (node (ref "IC8") (pin "F10") (pinfunction "DPCLK2,_DIFFOUT_R30n_F10") (pintype "bidirectional"))
    )
    (net (code "113") (name "/RAPI_SPI0_CE0") (class "Default")
      (node (ref "IC8") (pin "E13") (pinfunction "CLK3n,_DIFFOUT_R20n_E13") (pintype "bidirectional"))
    )
    (net (code "114") (name "/RAPI_SPI0_MISO") (class "Default")
      (node (ref "IC8") (pin "K8") (pinfunction "CLK7p,_DIFFOUT_B20p_K8") (pintype "bidirectional"))
    )
    (net (code "115") (name "/RAPI_SPI0_MOSI") (class "Default")
      (node (ref "IC8") (pin "M11") (pinfunction "CLK6n,_DIFFOUT_B18n_M11") (pintype "bidirectional"))
    )
    (net (code "116") (name "/RAPI_SPI0_SCLK") (class "Default")
      (node (ref "IC8") (pin "F13") (pinfunction "CLK3p,_DIFFOUT_R20p_F13") (pintype "bidirectional"))
    )
    (net (code "117") (name "/RAPI_SPI1_CE0") (class "Default")
      (node (ref "IC8") (pin "A10") (pinfunction "DIFFOUT_T29p_A10") (pintype "bidirectional"))
    )
    (net (code "118") (name "/RAPI_SPI1_MISO") (class "Default")
      (node (ref "IC8") (pin "L11") (pinfunction "CLK6p,_DIFFOUT_B18p_L11") (pintype "bidirectional"))
    )
    (net (code "119") (name "/RAPI_SPI1_MOSI") (class "Default")
      (node (ref "IC8") (pin "K13") (pinfunction "I/O_K13") (pintype "bidirectional"))
    )
    (net (code "120") (name "/RAPI_SPI1_SCLK") (class "Default")
      (node (ref "IC8") (pin "G10") (pinfunction "CLK2n,_DIFFOUT_R18n_G10") (pintype "bidirectional"))
    )
    (net (code "121") (name "/SR_DIN") (class "Default")
      (node (ref "IC8") (pin "B7") (pinfunction "VREFB8N0_B7") (pintype "bidirectional"))
    )
    (net (code "122") (name "/SR_LATCH") (class "Default")
      (node (ref "IC8") (pin "D6") (pinfunction "CRC_ERROR,_DIFFOUT_T34n_D6") (pintype "bidirectional"))
    )
    (net (code "123") (name "/SR_SCLK") (class "Default")
      (node (ref "IC8") (pin "B9") (pinfunction "DEV_CLRn,_DIFFOUT_T28n_B9") (pintype "bidirectional"))
      (node (ref "R48") (pin "2") (pinfunction "2_2") (pintype "passive"))
    )
    (net (code "124") (name "/WIFI_PIO5") (class "Default")
      (node (ref "IC8") (pin "C9") (pinfunction "CLK5n,_DIFFOUT_T26n_C9") (pintype "bidirectional"))
    )
    (net (code "125") (name "GND") (class "Default")
      (node (ref "C100") (pin "2") (pinfunction "2_2") (pintype "passive"))
      (node (ref "C101") (pin "2") (pinfunction "2_2") (pintype "passive"))
      (node (ref "C102") (pin "2") (pinfunction "2_2") (pintype "passive"))
      (node (ref "C103") (pin "2") (pinfunction "2_2") (pintype "passive"))
      (node (ref "C104") (pin "2") (pinfunction "2_2") (pintype "passive"))
      (node (ref "C105") (pin "1") (pinfunction "1_1") (pintype "passive"))
      (node (ref "C106") (pin "2") (pinfunction "2_2") (pintype "passive"))
      (node (ref "C107") (pin "2") (pinfunction "2_2") (pintype "passive"))
      (node (ref "C108") (pin "2") (pinfunction "2_2") (pintype "passive"))
      (node (ref "C109") (pin "1") (pinfunction "1_1") (pintype "passive"))
      (node (ref "C110") (pin "2") (pinfunction "2_2") (pintype "passive"))
      (node (ref "C111") (pin "2") (pinfunction "2_2") (pintype "passive"))
      (node (ref "C112") (pin "2") (pinfunction "2_2") (pintype "passive"))
      (node (ref "C113") (pin "2") (pinfunction "2_2") (pintype "passive"))
      (node (ref "C114") (pin "2") (pinfunction "2_2") (pintype "passive"))
      (node (ref "C115") (pin "2") (pinfunction "2_2") (pintype "passive"))
      (node (ref "C116") (pin "2") (pinfunction "2_2") (pintype "passive"))
      (node (ref "C117") (pin "2") (pinfunction "2_2") (pintype "passive"))
      (node (ref "C84") (pin "1") (pinfunction "1_1") (pintype "passive"))
      (node (ref "C85") (pin "1") (pinfunction "1_1") (pintype "passive"))
      (node (ref "C86") (pin "2") (pinfunction "2_2") (pintype "passive"))
      (node (ref "C87") (pin "2") (pinfunction "2_2") (pintype "passive"))
      (node (ref "C88") (pin "2") (pinfunction "2_2") (pintype "passive"))
      (node (ref "C89") (pin "2") (pinfunction "2_2") (pintype "passive"))
      (node (ref "C90") (pin "2") (pinfunction "2_2") (pintype "passive"))
      (node (ref "C91") (pin "2") (pinfunction "2_2") (pintype "passive"))
      (node (ref "C92") (pin "1") (pinfunction "1_1") (pintype "passive"))
      (node (ref "C93") (pin "2") (pinfunction "2_2") (pintype "passive"))
      (node (ref "C94") (pin "2") (pinfunction "2_2") (pintype "passive"))
      (node (ref "C95") (pin "2") (pinfunction "2_2") (pintype "passive"))
      (node (ref "C96") (pin "2") (pinfunction "2_2") (pintype "passive"))
      (node (ref "C97") (pin "2") (pinfunction "2_2") (pintype "passive"))
      (node (ref "C98") (pin "2") (pinfunction "2_2") (pintype "passive"))
      (node (ref "C99") (pin "1") (pinfunction "1_1") (pintype "passive"))
      (node (ref "IC8") (pin "A1") (pinfunction "GND_A1") (pintype "passive"))
      (node (ref "IC8") (pin "A13") (pinfunction "GND_A13") (pintype "passive"))
      (node (ref "IC8") (pin "B8") (pinfunction "GND_B8") (pintype "passive"))
      (node (ref "IC8") (pin "C3") (pinfunction "GND_C3") (pintype "passive"))
      (node (ref "IC8") (pin "D2") (pinfunction "ANAIN1_D2") (pintype "passive"))
      (node (ref "IC8") (pin "D5") (pinfunction "GND_D5") (pintype "passive"))
      (node (ref "IC8") (pin "E11") (pinfunction "GND_E11") (pintype "passive"))
      (node (ref "IC8") (pin "E2") (pinfunction "REFGND_E2") (pintype "passive"))
      (node (ref "IC8") (pin "E3") (pinfunction "DIFFOUT_L3n_E3") (pintype "bidirectional"))
      (node (ref "IC8") (pin "F3") (pinfunction "GND_F3") (pintype "passive"))
      (node (ref "IC8") (pin "F4") (pinfunction "DIFFOUT_L14n_F4") (pintype "bidirectional"))
      (node (ref "IC8") (pin "G7") (pinfunction "GND_G7") (pintype "passive"))
      (node (ref "IC8") (pin "H12") (pinfunction "GND_H12") (pintype "passive"))
      (node (ref "IC8") (pin "J4") (pinfunction "GND_J4") (pintype "passive"))
      (node (ref "IC8") (pin "L9") (pinfunction "GND_L9") (pintype "passive"))
      (node (ref "IC8") (pin "M6") (pinfunction "GND_M6") (pintype "passive"))
      (node (ref "IC8") (pin "N1") (pinfunction "GND_N1") (pintype "passive"))
      (node (ref "IC8") (pin "N13") (pinfunction "GND_N13") (pintype "passive"))
      (node (ref "J3") (pin "1") (pinfunction "1_1") (pintype "passive"))
      (node (ref "J4") (pin "10") (pinfunction "10_10") (pintype "passive"))
      (node (ref "J4") (pin "2") (pinfunction "2_2") (pintype "passive"))
      (node (ref "J5") (pin "9") (pinfunction "9_9") (pintype "passive"))
      (node (ref "R40") (pin "1") (pinfunction "1_1") (pintype "passive"))
      (node (ref "R41") (pin "2") (pinfunction "2_2") (pintype "passive"))
      (node (ref "R44") (pin "1") (pinfunction "1_1") (pintype "passive"))
      (node (ref "R45") (pin "1") (pinfunction "1_1") (pintype "passive"))
      (node (ref "R46") (pin "1") (pinfunction "1_1") (pintype "passive"))
      (node (ref "R47") (pin "1") (pinfunction "1_1") (pintype "passive"))
    )
    (net (code "126") (name "Net-(C84-Pad2)") (class "Default")
      (node (ref "C84") (pin "2") (pinfunction "2_2") (pintype "passive"))
      (node (ref "J5") (pin "10") (pinfunction "10_10") (pintype "passive"))
      (node (ref "R42") (pin "2") (pinfunction "2_2") (pintype "passive"))
      (node (ref "R43") (pin "2") (pinfunction "2_2") (pintype "passive"))
    )
    (net (code "127") (name "Net-(IC8A-JTAGEN)") (class "Default")
      (node (ref "IC8") (pin "E5") (pinfunction "JTAGEN_E5") (pintype "bidirectional"))
      (node (ref "R39") (pin "2") (pinfunction "2_2") (pintype "passive"))
    )
    (net (code "128") (name "Net-(IC8F-nCONFIG)") (class "Default")
      (node (ref "IC8") (pin "E7") (pinfunction "nCONFIG_E7") (pintype "input"))
      (node (ref "R50") (pin "2") (pinfunction "2_2") (pintype "passive"))
    )
    (net (code "129") (name "Net-(IC8F-nSTATUS,_DIFFOUT_T36p)") (class "Default")
      (node (ref "IC8") (pin "C4") (pinfunction "nSTATUS,_DIFFOUT_T36p_C4") (pintype "bidirectional"))
      (node (ref "R51") (pin "2") (pinfunction "2_2") (pintype "passive"))
    )
    (net (code "130") (name "VCC1P8") (class "Default")
      (node (ref "C105") (pin "2") (pinfunction "2_2") (pintype "passive"))
      (node (ref "C106") (pin "1") (pinfunction "1_1") (pintype "passive"))
      (node (ref "C107") (pin "1") (pinfunction "1_1") (pintype "passive"))
      (node (ref "C108") (pin "1") (pinfunction "1_1") (pintype "passive"))
      (node (ref "IC8") (pin "F2") (pinfunction "VCCIO1A_F2") (pintype "passive"))
      (node (ref "IC8") (pin "G3") (pinfunction "VCCIO1B_G3") (pintype "passive"))
      (node (ref "J3") (pin "6") (pinfunction "6_6") (pintype "passive"))
      (node (ref "J4") (pin "4") (pinfunction "4_4") (pintype "passive"))
      (node (ref "R36") (pin "2") (pinfunction "2_2") (pintype "passive"))
      (node (ref "R38") (pin "2") (pinfunction "2_2") (pintype "passive"))
      (node (ref "R39") (pin "1") (pinfunction "1_1") (pintype "passive"))
    )
    (net (code "131") (name "VCC3P3") (class "Default")
      (node (ref "C100") (pin "1") (pinfunction "1_1") (pintype "passive"))
      (node (ref "C101") (pin "1") (pinfunction "1_1") (pintype "passive"))
      (node (ref "C102") (pin "1") (pinfunction "1_1") (pintype "passive"))
      (node (ref "C103") (pin "1") (pinfunction "1_1") (pintype "passive"))
      (node (ref "C104") (pin "1") (pinfunction "1_1") (pintype "passive"))
      (node (ref "C109") (pin "2") (pinfunction "2_2") (pintype "passive"))
      (node (ref "C110") (pin "1") (pinfunction "1_1") (pintype "passive"))
      (node (ref "C111") (pin "1") (pinfunction "1_1") (pintype "passive"))
      (node (ref "C112") (pin "1") (pinfunction "1_1") (pintype "passive"))
      (node (ref "C113") (pin "1") (pinfunction "1_1") (pintype "passive"))
      (node (ref "C114") (pin "1") (pinfunction "1_1") (pintype "passive"))
      (node (ref "C115") (pin "1") (pinfunction "1_1") (pintype "passive"))
      (node (ref "C116") (pin "1") (pinfunction "1_1") (pintype "passive"))
      (node (ref "C117") (pin "1") (pinfunction "1_1") (pintype "passive"))
      (node (ref "C85") (pin "2") (pinfunction "2_2") (pintype "passive"))
      (node (ref "C86") (pin "1") (pinfunction "1_1") (pintype "passive"))
      (node (ref "C87") (pin "1") (pinfunction "1_1") (pintype "passive"))
      (node (ref "C88") (pin "1") (pinfunction "1_1") (pintype "passive"))
      (node (ref "C89") (pin "1") (pinfunction "1_1") (pintype "passive"))
      (node (ref "C90") (pin "1") (pinfunction "1_1") (pintype "passive"))
      (node (ref "C91") (pin "1") (pinfunction "1_1") (pintype "passive"))
      (node (ref "C99") (pin "2") (pinfunction "2_2") (pintype "passive"))
      (node (ref "FR35") (pin "1") (pinfunction "1_1") (pintype "passive"))
      (node (ref "IC8") (pin "C6") (pinfunction "VCCIO8_C6") (pintype "passive"))
      (node (ref "IC8") (pin "C7") (pinfunction "VCCIO8_C7") (pintype "passive"))
      (node (ref "IC8") (pin "C8") (pinfunction "VCCIO8_C8") (pintype "passive"))
      (node (ref "IC8") (pin "F11") (pinfunction "VCCIO6_F11") (pintype "passive"))
      (node (ref "IC8") (pin "F7") (pinfunction "VCC_ONE_F7") (pintype "passive"))
      (node (ref "IC8") (pin "G11") (pinfunction "VCCIO6_G11") (pintype "passive"))
      (node (ref "IC8") (pin "G6") (pinfunction "VCC_ONE_G6") (pintype "passive"))
      (node (ref "IC8") (pin "G8") (pinfunction "VCC_ONE_G8") (pintype "passive"))
      (node (ref "IC8") (pin "H11") (pinfunction "VCCIO5_H11") (pintype "passive"))
      (node (ref "IC8") (pin "H7") (pinfunction "VCC_ONE_H7") (pintype "passive"))
      (node (ref "IC8") (pin "J11") (pinfunction "VCCIO5_J11") (pintype "passive"))
      (node (ref "IC8") (pin "J3") (pinfunction "VCCIO2_J3") (pintype "passive"))
      (node (ref "IC8") (pin "K3") (pinfunction "VCCIO2_K3") (pintype "passive"))
      (node (ref "IC8") (pin "L6") (pinfunction "VCCIO3_L6") (pintype "passive"))
      (node (ref "IC8") (pin "L7") (pinfunction "VCCIO3_L7") (pintype "passive"))
      (node (ref "IC8") (pin "L8") (pinfunction "VCCIO3_L8") (pintype "passive"))
      (node (ref "R37") (pin "1") (pinfunction "1_1") (pintype "passive"))
      (node (ref "R42") (pin "1") (pinfunction "1_1") (pintype "passive"))
      (node (ref "R48") (pin "1") (pinfunction "1_1") (pintype "passive"))
      (node (ref "R49") (pin "1") (pinfunction "1_1") (pintype "passive"))
      (node (ref "R50") (pin "1") (pinfunction "1_1") (pintype "passive"))
      (node (ref "R51") (pin "1") (pinfunction "1_1") (pintype "passive"))
      (node (ref "R52") (pin "1") (pinfunction "1_1") (pintype "passive"))
    )
    (net (code "132") (name "VCC3P3A") (class "Default")
      (node (ref "C92") (pin "2") (pinfunction "2_2") (pintype "passive"))
      (node (ref "C93") (pin "1") (pinfunction "1_1") (pintype "passive"))
      (node (ref "C94") (pin "1") (pinfunction "1_1") (pintype "passive"))
      (node (ref "C95") (pin "1") (pinfunction "1_1") (pintype "passive"))
      (node (ref "C96") (pin "1") (pinfunction "1_1") (pintype "passive"))
      (node (ref "C97") (pin "1") (pinfunction "1_1") (pintype "passive"))
      (node (ref "C98") (pin "1") (pinfunction "1_1") (pintype "passive"))
      (node (ref "FR35") (pin "2") (pinfunction "2_2") (pintype "passive"))
      (node (ref "IC8") (pin "D10") (pinfunction "VCCA2_D10") (pintype "passive"))
      (node (ref "IC8") (pin "D3") (pinfunction "ADC_VREF_D3") (pintype "passive"))
      (node (ref "IC8") (pin "D4") (pinfunction "VCCA3_D4") (pintype "passive"))
      (node (ref "IC8") (pin "K4") (pinfunction "VCCA1_K4") (pintype "passive"))
      (node (ref "IC8") (pin "K9") (pinfunction "VCCA4_K9") (pintype "passive"))
    )
    (net (code "133") (name "VCC5P0") (class "Default")
      (node (ref "J3") (pin "7") (pinfunction "7_7") (pintype "passive"))
      (node (ref "R43") (pin "1") (pinfunction "1_1") (pintype "passive"))
    )
    (net (code "134") (name "unconnected-(IC8A-DIFFOUT_L3p-PadE4)") (class "Default")
      (node (ref "IC8") (pin "E4") (pinfunction "DIFFOUT_L3p_E4") (pintype "bidirectional+no_connect"))
    )
    (net (code "135") (name "unconnected-(J4-Pad6)") (class "Default")
      (node (ref "J4") (pin "6") (pinfunction "6_6") (pintype "passive+no_connect"))
    )
    (net (code "136") (name "unconnected-(J4-Pad7)") (class "Default")
      (node (ref "J4") (pin "7") (pinfunction "7_7") (pintype "passive+no_connect"))
    )
    (net (code "137") (name "unconnected-(J4-Pad8)") (class "Default")
      (node (ref "J4") (pin "8") (pinfunction "8_8") (pintype "passive+no_connect"))
    )
  )
)
